# VoxPopuli.net
KiCad netlist of a schematic drawn in Altium Designer
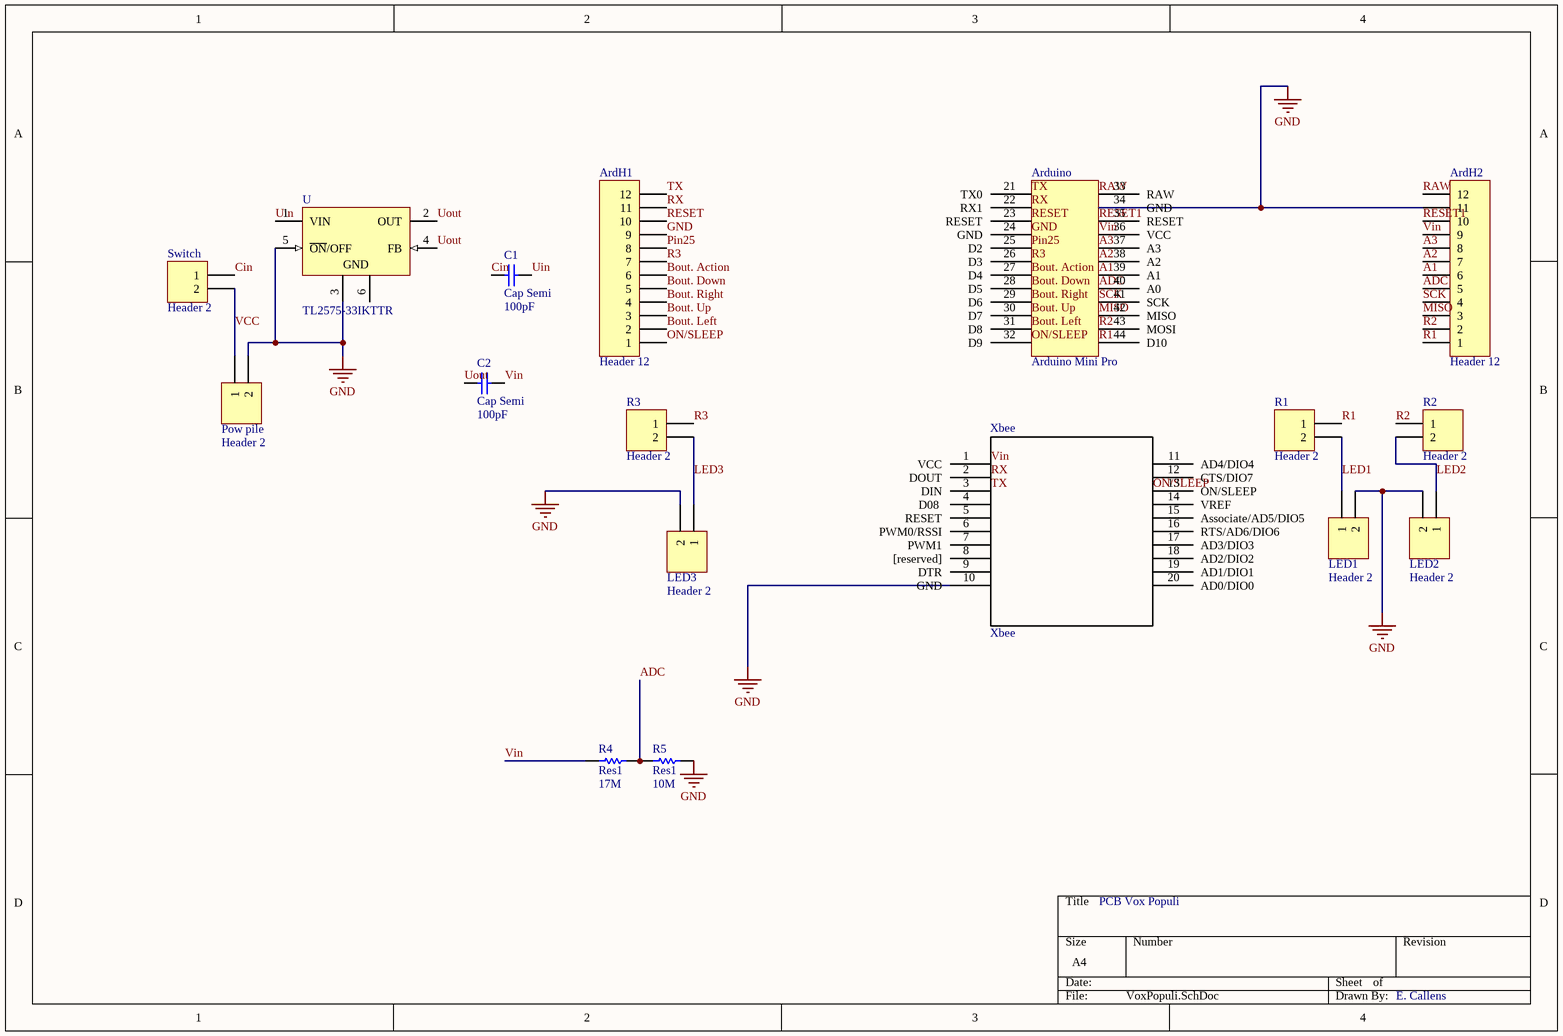
[diagram p0: VoxPopuli.SchDoc]

(export (version "E")
  (design (tool "Eeschema 10.0.6"))
  (components
    (comp (ref "ArdH1")
      (value "Header 12")
      (footprint "HEADER 12")
      (description "Header, 12-Pin")
      (fields (field (name "PUBLISHER") "Altium Limited"))
      (libsource (lib "Miscellaneous Connectors") (part "Header 12"))
    )
    (comp (ref "ArdH2")
      (value "Header 12")
      (footprint "HEADER 12")
      (description "Header, 12-Pin")
      (fields (field (name "PUBLISHER") "Altium Limited"))
      (libsource (lib "") (part "Header 12_1"))
    )
    (comp (ref "Arduino")
      (value "Arduino Mini Pro")
      (footprint "ARDUINO DIP 2")
      (description "Arduino Board")
      (libsource (lib "VoxPopuli") (part "Arduino Mini Pro"))
    )
    (comp (ref "C1")
      (value "Cap Semi")
      (footprint "C1206")
      (description "Capacitor (Semiconductor SIM Model)")
      (fields (field (name "ALTIUM_VALUE") "100pF") (field (name "PUBLISHER") "Altium Limited"))
      (libsource (lib "Miscellaneous Devices") (part "Cap Semi"))
    )
    (comp (ref "C2")
      (value "Cap Semi")
      (footprint "C1206")
      (description "Capacitor (Semiconductor SIM Model)")
      (fields (field (name "ALTIUM_VALUE") "100pF") (field (name "PUBLISHER") "Altium Limited"))
      (libsource (lib "Miscellaneous Devices") (part "Cap Semi"))
    )
    (comp (ref "LED1")
      (value "Header 2")
      (footprint "HEADER 2")
      (description "Header, 2-Pin")
      (fields (field (name "PUBLISHER") "Altium Limited"))
      (libsource (lib "") (part "Header 2_1"))
    )
    (comp (ref "LED2")
      (value "Header 2")
      (footprint "HEADER 2")
      (description "Header, 2-Pin")
      (fields (field (name "PUBLISHER") "Altium Limited"))
      (libsource (lib "Miscellaneous Connectors") (part "Header 2"))
    )
    (comp (ref "LED3")
      (value "Header 2")
      (footprint "HEADER 2")
      (description "Header, 2-Pin")
      (fields (field (name "PUBLISHER") "Altium Limited"))
      (libsource (lib "Miscellaneous Connectors") (part "Header 2"))
    )
    (comp (ref "Pow pile")
      (value "Header 2")
      (footprint "HEADER 2")
      (description "Header, 2-Pin")
      (fields (field (name "PUBLISHER") "Altium Limited"))
      (libsource (lib "") (part "Header 2_1"))
    )
    (comp (ref "R1")
      (value "Header 2")
      (footprint "HEADER 2")
      (description "Header, 2-Pin")
      (fields (field (name "PUBLISHER") "Altium Limited"))
      (libsource (lib "Miscellaneous Connectors") (part "Header 2"))
    )
    (comp (ref "R2")
      (value "Header 2")
      (footprint "HEADER 2")
      (description "Header, 2-Pin")
      (fields (field (name "PUBLISHER") "Altium Limited"))
      (libsource (lib "") (part "Header 2_2"))
    )
    (comp (ref "R3")
      (value "Header 2")
      (footprint "HEADER 2")
      (description "Header, 2-Pin")
      (fields (field (name "PUBLISHER") "Altium Limited"))
      (libsource (lib "Miscellaneous Connectors") (part "Header 2"))
    )
    (comp (ref "R4")
      (value "Res1")
      (footprint "C1206")
      (description "Resistor")
      (fields (field (name "ALTIUM_VALUE") "17M") (field (name "PUBLISHER") "Altium Limited"))
      (libsource (lib "Miscellaneous Devices") (part "Res1"))
    )
    (comp (ref "R5")
      (value "Res1")
      (footprint "C1206")
      (description "Resistor")
      (fields (field (name "ALTIUM_VALUE") "10M") (field (name "PUBLISHER") "Altium Limited"))
      (libsource (lib "Miscellaneous Devices") (part "Res1"))
    )
    (comp (ref "Switch")
      (value "Header 2")
      (footprint "HEADER 2")
      (description "Header, 2-Pin")
      (fields (field (name "PUBLISHER") "Altium Limited"))
      (libsource (lib "Miscellaneous Connectors") (part "Header 2"))
    )
    (comp (ref "U")
      (value "TL2575-33IKTTR")
      (footprint "KTT5_N")
      (fields (field (name "MANUFACTURER") "Texas Instruments"))
      (libsource (lib "TI Power Management Step-Down Regulator") (part "TL2575-33IKTTR"))
    )
    (comp (ref "Xbee")
      (value "Xbee")
      (footprint "XBEE DIP 2")
      (description "Xbee Card")
      (libsource (lib "VoxPopuli") (part "Xbee"))
    )
  )
  (nets
    (net (code "1") (name "/A1") (class "Default")
      (node (ref "ArdH2") (pin "6") (pinfunction "6_6") (pintype "passive"))
      (node (ref "Arduino") (pin "39") (pinfunction "A1_39") (pintype "passive"))
    )
    (net (code "2") (name "/A2") (class "Default")
      (node (ref "ArdH2") (pin "7") (pinfunction "7_7") (pintype "passive"))
      (node (ref "Arduino") (pin "38") (pinfunction "A2_38") (pintype "passive"))
    )
    (net (code "3") (name "/A3") (class "Default")
      (node (ref "ArdH2") (pin "8") (pinfunction "8_8") (pintype "passive"))
      (node (ref "Arduino") (pin "37") (pinfunction "A3_37") (pintype "passive"))
    )
    (net (code "4") (name "/ADC") (class "Default")
      (node (ref "ArdH2") (pin "5") (pinfunction "5_5") (pintype "passive"))
      (node (ref "Arduino") (pin "40") (pinfunction "A0_40") (pintype "passive"))
      (node (ref "R4") (pin "2") (pinfunction "2_2") (pintype "passive"))
      (node (ref "R5") (pin "1") (pinfunction "1_1") (pintype "passive"))
    )
    (net (code "5") (name "/Bout. Action") (class "Default")
      (node (ref "ArdH1") (pin "6") (pinfunction "6_6") (pintype "passive"))
      (node (ref "Arduino") (pin "27") (pinfunction "D4_27") (pintype "passive"))
    )
    (net (code "6") (name "/Bout. Down") (class "Default")
      (node (ref "ArdH1") (pin "5") (pinfunction "5_5") (pintype "passive"))
      (node (ref "Arduino") (pin "28") (pinfunction "D5_28") (pintype "passive"))
    )
    (net (code "7") (name "/Bout. Left") (class "Default")
      (node (ref "ArdH1") (pin "2") (pinfunction "2_2") (pintype "passive"))
      (node (ref "Arduino") (pin "31") (pinfunction "D8_31") (pintype "passive"))
    )
    (net (code "8") (name "/Bout. Right") (class "Default")
      (node (ref "ArdH1") (pin "4") (pinfunction "4_4") (pintype "passive"))
      (node (ref "Arduino") (pin "29") (pinfunction "D6_29") (pintype "passive"))
    )
    (net (code "9") (name "/Bout. Up") (class "Default")
      (node (ref "ArdH1") (pin "3") (pinfunction "3_3") (pintype "passive"))
      (node (ref "Arduino") (pin "30") (pinfunction "D7_30") (pintype "passive"))
    )
    (net (code "10") (name "/Cin") (class "Default")
      (node (ref "C1") (pin "1") (pinfunction "1_1") (pintype "passive"))
      (node (ref "Switch") (pin "1") (pinfunction "1_1") (pintype "passive"))
    )
    (net (code "11") (name "/LED1") (class "Default")
      (node (ref "LED1") (pin "1") (pinfunction "1_1") (pintype "passive"))
      (node (ref "R1") (pin "2") (pinfunction "2_2") (pintype "passive"))
    )
    (net (code "12") (name "/LED2") (class "Default")
      (node (ref "LED2") (pin "1") (pinfunction "1_1") (pintype "passive"))
      (node (ref "R2") (pin "2") (pinfunction "2_2") (pintype "passive"))
    )
    (net (code "13") (name "/LED3") (class "Default")
      (node (ref "LED3") (pin "1") (pinfunction "1_1") (pintype "passive"))
      (node (ref "R3") (pin "2") (pinfunction "2_2") (pintype "passive"))
    )
    (net (code "14") (name "/MISO") (class "Default")
      (node (ref "ArdH2") (pin "3") (pinfunction "3_3") (pintype "passive"))
      (node (ref "Arduino") (pin "42") (pinfunction "MISO_42") (pintype "passive"))
    )
    (net (code "15") (name "/ON{slash}SLEEP") (class "Default")
      (node (ref "ArdH1") (pin "1") (pinfunction "1_1") (pintype "passive"))
      (node (ref "Arduino") (pin "32") (pinfunction "D9_32") (pintype "passive"))
      (node (ref "Xbee") (pin "13") (pinfunction "ON/SLEEP_13") (pintype "passive"))
    )
    (net (code "16") (name "/Pin25") (class "Default")
      (node (ref "ArdH1") (pin "8") (pinfunction "8_8") (pintype "passive"))
      (node (ref "Arduino") (pin "25") (pinfunction "D2_25") (pintype "passive"))
    )
    (net (code "17") (name "/R1") (class "Default")
      (node (ref "ArdH2") (pin "1") (pinfunction "1_1") (pintype "passive"))
      (node (ref "Arduino") (pin "44") (pinfunction "D10_44") (pintype "passive"))
      (node (ref "R1") (pin "1") (pinfunction "1_1") (pintype "passive"))
    )
    (net (code "18") (name "/R2") (class "Default")
      (node (ref "ArdH2") (pin "2") (pinfunction "2_2") (pintype "passive"))
      (node (ref "Arduino") (pin "43") (pinfunction "MOSI_43") (pintype "passive"))
      (node (ref "R2") (pin "1") (pinfunction "1_1") (pintype "passive"))
    )
    (net (code "19") (name "/R3") (class "Default")
      (node (ref "ArdH1") (pin "7") (pinfunction "7_7") (pintype "passive"))
      (node (ref "Arduino") (pin "26") (pinfunction "D3_26") (pintype "passive"))
      (node (ref "R3") (pin "1") (pinfunction "1_1") (pintype "passive"))
    )
    (net (code "20") (name "/RAW") (class "Default")
      (node (ref "ArdH2") (pin "12") (pinfunction "12_12") (pintype "passive"))
      (node (ref "Arduino") (pin "33") (pinfunction "RAW_33") (pintype "passive"))
    )
    (net (code "21") (name "/RESET") (class "Default")
      (node (ref "ArdH1") (pin "10") (pinfunction "10_10") (pintype "passive"))
      (node (ref "Arduino") (pin "23") (pinfunction "RESET_23") (pintype "passive"))
    )
    (net (code "22") (name "/RESET1") (class "Default")
      (node (ref "ArdH2") (pin "10") (pinfunction "10_10") (pintype "passive"))
      (node (ref "Arduino") (pin "35") (pinfunction "RESET_35") (pintype "passive"))
    )
    (net (code "23") (name "/RX") (class "Default")
      (node (ref "ArdH1") (pin "11") (pinfunction "11_11") (pintype "passive"))
      (node (ref "Arduino") (pin "22") (pinfunction "RX1_22") (pintype "passive"))
      (node (ref "Xbee") (pin "2") (pinfunction "DOUT_2") (pintype "passive"))
    )
    (net (code "24") (name "/SCK") (class "Default")
      (node (ref "ArdH2") (pin "4") (pinfunction "4_4") (pintype "passive"))
      (node (ref "Arduino") (pin "41") (pinfunction "SCK_41") (pintype "passive"))
    )
    (net (code "25") (name "/TX") (class "Default")
      (node (ref "ArdH1") (pin "12") (pinfunction "12_12") (pintype "passive"))
      (node (ref "Arduino") (pin "21") (pinfunction "TX0_21") (pintype "passive"))
      (node (ref "Xbee") (pin "3") (pinfunction "DIN_3") (pintype "passive"))
    )
    (net (code "26") (name "/Uin") (class "Default")
      (node (ref "C1") (pin "2") (pinfunction "2_2") (pintype "passive"))
      (node (ref "U") (pin "1") (pinfunction "VIN_1") (pintype "power_in"))
    )
    (net (code "27") (name "/Uout") (class "Default")
      (node (ref "C2") (pin "1") (pinfunction "1_1") (pintype "passive"))
      (node (ref "U") (pin "2") (pinfunction "OUT_2") (pintype "power_in"))
      (node (ref "U") (pin "4") (pinfunction "FB_4") (pintype "input"))
    )
    (net (code "28") (name "/VCC") (class "Default")
      (node (ref "Pow pile") (pin "1") (pinfunction "1_1") (pintype "passive"))
      (node (ref "Switch") (pin "2") (pinfunction "2_2") (pintype "passive"))
    )
    (net (code "29") (name "/Vin") (class "Default")
      (node (ref "ArdH2") (pin "9") (pinfunction "9_9") (pintype "passive"))
      (node (ref "Arduino") (pin "36") (pinfunction "VCC_36") (pintype "passive"))
      (node (ref "C2") (pin "2") (pinfunction "2_2") (pintype "passive"))
      (node (ref "R4") (pin "1") (pinfunction "1_1") (pintype "passive"))
      (node (ref "Xbee") (pin "1") (pinfunction "VCC_1") (pintype "passive"))
    )
    (net (code "30") (name "GND") (class "Default")
      (node (ref "ArdH1") (pin "9") (pinfunction "9_9") (pintype "passive"))
      (node (ref "ArdH2") (pin "11") (pinfunction "11_11") (pintype "passive"))
      (node (ref "Arduino") (pin "24") (pinfunction "GND_24") (pintype "passive"))
      (node (ref "Arduino") (pin "34") (pinfunction "GND_34") (pintype "passive"))
      (node (ref "LED1") (pin "2") (pinfunction "2_2") (pintype "passive"))
      (node (ref "LED2") (pin "2") (pinfunction "2_2") (pintype "passive"))
      (node (ref "LED3") (pin "2") (pinfunction "2_2") (pintype "passive"))
      (node (ref "Pow pile") (pin "2") (pinfunction "2_2") (pintype "passive"))
      (node (ref "R5") (pin "2") (pinfunction "2_2") (pintype "passive"))
      (node (ref "U") (pin "3") (pinfunction "GND_3") (pintype "power_in"))
      (node (ref "U") (pin "5") (pinfunction "~{ON}/OFF_5") (pintype "input"))
      (node (ref "Xbee") (pin "10") (pinfunction "GND_10") (pintype "passive"))
    )
    (net (code "31") (name "unconnected-(U-GND-Pad6)") (class "Default")
      (node (ref "U") (pin "6") (pinfunction "GND_6") (pintype "power_in"))
    )
    (net (code "32") (name "unconnected-(Xbee-AD0{slash}DIO0-Pad20)") (class "Default")
      (node (ref "Xbee") (pin "20") (pinfunction "AD0/DIO0_20") (pintype "passive"))
    )
    (net (code "33") (name "unconnected-(Xbee-AD1{slash}DIO1-Pad19)") (class "Default")
      (node (ref "Xbee") (pin "19") (pinfunction "AD1/DIO1_19") (pintype "passive"))
    )
    (net (code "34") (name "unconnected-(Xbee-AD2{slash}DIO2-Pad18)") (class "Default")
      (node (ref "Xbee") (pin "18") (pinfunction "AD2/DIO2_18") (pintype "passive"))
    )
    (net (code "35") (name "unconnected-(Xbee-AD3{slash}DIO3-Pad17)") (class "Default")
      (node (ref "Xbee") (pin "17") (pinfunction "AD3/DIO3_17") (pintype "passive"))
    )
    (net (code "36") (name "unconnected-(Xbee-AD4{slash}DIO4-Pad11)") (class "Default")
      (node (ref "Xbee") (pin "11") (pinfunction "AD4/DIO4_11") (pintype "passive"))
    )
    (net (code "37") (name "unconnected-(Xbee-Associate{slash}AD5{slash}DIO5-Pad15)") (class "Default")
      (node (ref "Xbee") (pin "15") (pinfunction "Associate/AD5/DIO5_15") (pintype "passive"))
    )
    (net (code "38") (name "unconnected-(Xbee-CTS{slash}DIO7-Pad12)") (class "Default")
      (node (ref "Xbee") (pin "12") (pinfunction "CTS/DIO7_12") (pintype "passive"))
    )
    (net (code "39") (name "unconnected-(Xbee-D08-Pad4)") (class "Default")
      (node (ref "Xbee") (pin "4") (pinfunction "D08_4") (pintype "passive"))
    )
    (net (code "40") (name "unconnected-(Xbee-DTR-Pad9)") (class "Default")
      (node (ref "Xbee") (pin "9") (pinfunction "DTR_9") (pintype "passive"))
    )
    (net (code "41") (name "unconnected-(Xbee-PWM0{slash}RSSI-Pad6)") (class "Default")
      (node (ref "Xbee") (pin "6") (pinfunction "PWM0/RSSI_6") (pintype "passive"))
    )
    (net (code "42") (name "unconnected-(Xbee-PWM1-Pad7)") (class "Default")
      (node (ref "Xbee") (pin "7") (pinfunction "PWM1_7") (pintype "passive"))
    )
    (net (code "43") (name "unconnected-(Xbee-RESET-Pad5)") (class "Default")
      (node (ref "Xbee") (pin "5") (pinfunction "RESET_5") (pintype "passive"))
    )
    (net (code "44") (name "unconnected-(Xbee-RTS{slash}AD6{slash}DIO6-Pad16)") (class "Default")
      (node (ref "Xbee") (pin "16") (pinfunction "RTS/AD6/DIO6_16") (pintype "passive"))
    )
    (net (code "45") (name "unconnected-(Xbee-VREF-Pad14)") (class "Default")
      (node (ref "Xbee") (pin "14") (pinfunction "VREF_14") (pintype "passive"))
    )
    (net (code "46") (name "unconnected-(Xbee-[reserved]-Pad8)") (class "Default")
      (node (ref "Xbee") (pin "8") (pinfunction "[reserved]_8") (pintype "passive"))
    )
  )
)
